# TIDA-010056_Page2.net
KiCad netlist of a schematic drawn in Altium Designer
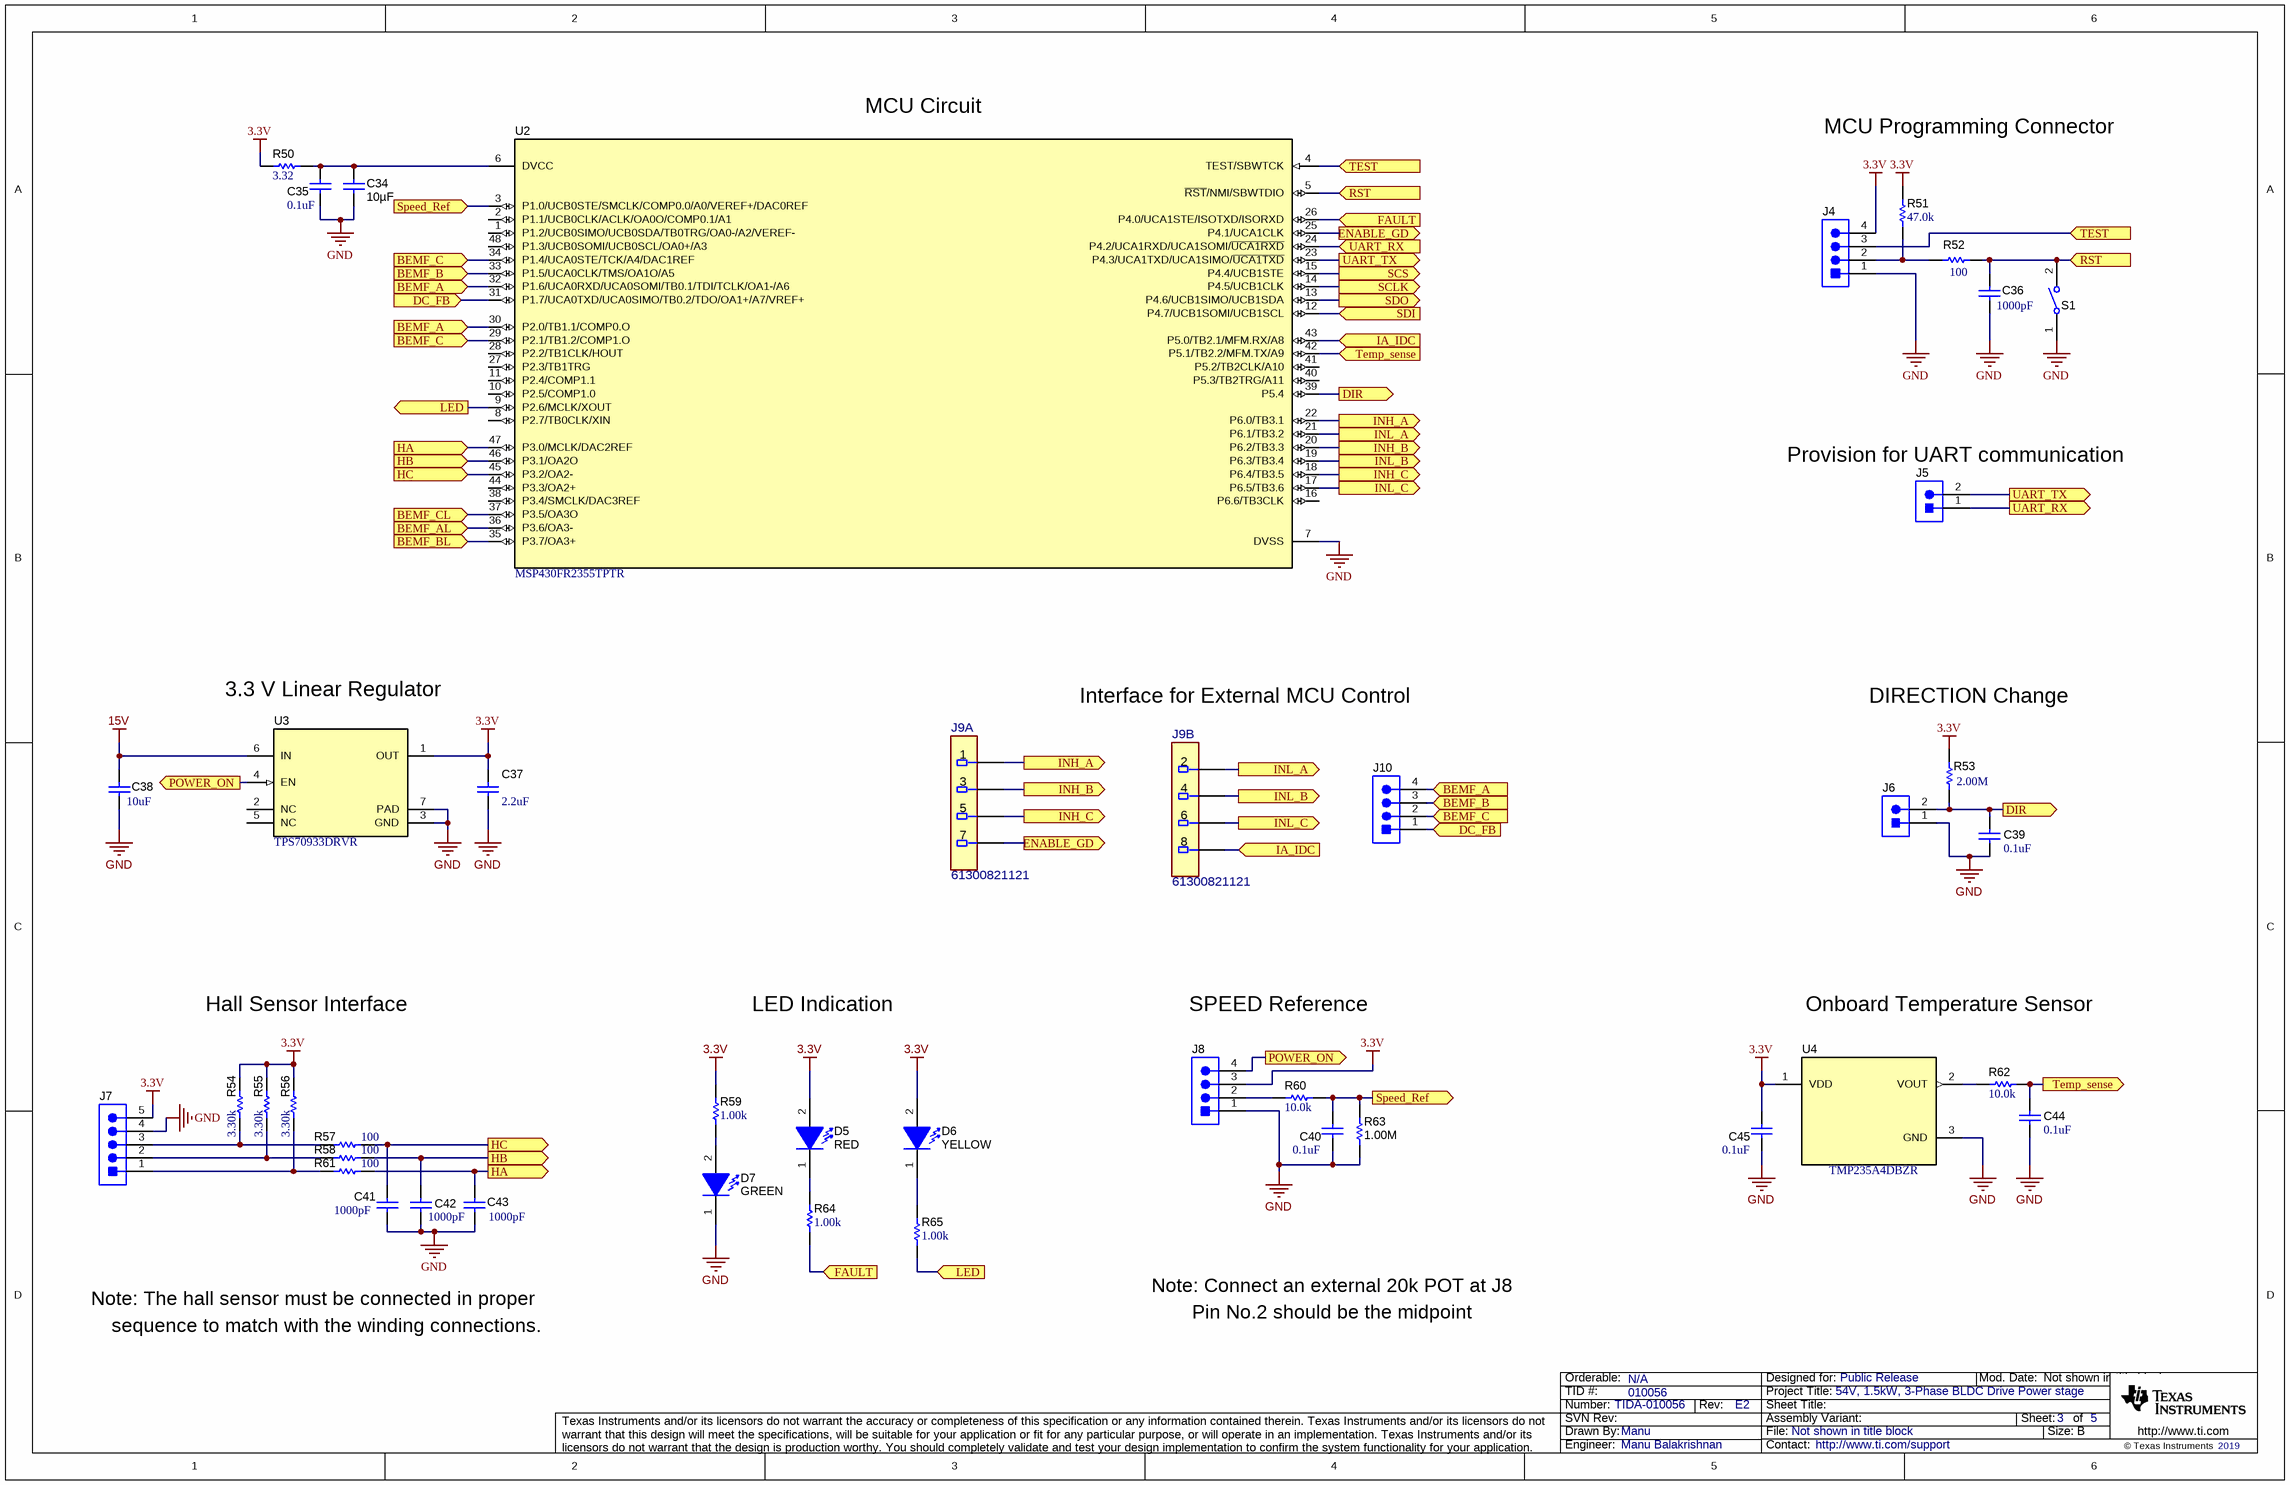
[diagram p0: TIDA-010056_Page2.SchDoc]

(export (version "E")
  (design (tool "Eeschema 10.0.6"))
  (components
    (comp (ref "C34")
      (value "GRM188R61A106KE69D")
      (footprint "0603")
      (description "CAP, CERM, 10 µF, 10 V,+/- 10%, X5R, 0603")
      (fields (field (name "MANUFACTURER") "MuRata") (field (name "VALUEDISPLAYED") "10µF"))
      (libsource (lib "Altium Vault - TI") (part "Capacitor"))
    )
    (comp (ref "C35")
      (value "GCM155R71A104KA55D")
      (footprint "0402")
      (description "CAP, CERM, 0.1 uF, 10 V, +/- 10%, X7R, AEC-Q200 Grade 1, 0402")
      (fields
        (field (name "MANUFACTURER") "MuRata")
        (field (name "VALUEDISPLAYED") "0.1uF")
        (field (name "PUBLISHER") "Texas Instruments")
      )
      (libsource (lib "Altium Vault - TI") (part "Capacitor"))
    )
    (comp (ref "C36")
      (value "GRM155R71C102KA01D")
      (footprint "0402")
      (description "CAP, CERM, 1000 pF, 16 V, +/- 10%, X7R, 0402")
      (fields
        (field (name "MANUFACTURER") "MuRata")
        (field (name "VALUEDISPLAYED") "1000pF")
        (field (name "PUBLISHER") "Texas Instruments")
      )
      (libsource (lib "Altium Vault - TI") (part "Capacitor"))
    )
    (comp (ref "C37")
      (value "885012105013")
      (footprint "0402")
      (description "CAP, CERM, 2.2 uF, 10 V, +/- 20%, X5R, 0402")
      (fields
        (field (name "MANUFACTURER") "Wurth Elektronik")
        (field (name "VALUEDISPLAYED") "2.2uF")
        (field (name "PUBLISHER") "Texas Instruments")
      )
      (libsource (lib "Altium Vault - TI") (part "Capacitor"))
    )
    (comp (ref "C38")
      (value "C3216X7R1V106M160AC")
      (footprint "1206_190")
      (description "CAP, CERM, 10 uF, 35 V, +/- 20%, X7R, 1206_190")
      (fields
        (field (name "MANUFACTURER") "TDK")
        (field (name "VALUEDISPLAYED") "10uF")
        (field (name "PUBLISHER") "Texas Instruments")
      )
      (libsource (lib "Altium Vault - TI") (part "Capacitor"))
    )
    (comp (ref "C39")
      (value "GCM155R71A104KA55D")
      (footprint "0402")
      (description "CAP, CERM, 0.1 uF, 10 V, +/- 10%, X7R, AEC-Q200 Grade 1, 0402")
      (fields
        (field (name "MANUFACTURER") "MuRata")
        (field (name "VALUEDISPLAYED") "0.1uF")
        (field (name "PUBLISHER") "Texas Instruments")
      )
      (libsource (lib "Altium Vault - TI") (part "Capacitor"))
    )
    (comp (ref "C40")
      (value "GCM155R71A104KA55D")
      (footprint "0402")
      (description "CAP, CERM, 0.1 uF, 10 V, +/- 10%, X7R, AEC-Q200 Grade 1, 0402")
      (fields
        (field (name "MANUFACTURER") "MuRata")
        (field (name "VALUEDISPLAYED") "0.1uF")
        (field (name "PUBLISHER") "Texas Instruments")
      )
      (libsource (lib "Altium Vault - TI") (part "Capacitor"))
    )
    (comp (ref "C41")
      (value "GRM155R71C102KA01D")
      (footprint "0402")
      (description "CAP, CERM, 1000 pF, 16 V, +/- 10%, X7R, 0402")
      (fields
        (field (name "MANUFACTURER") "MuRata")
        (field (name "VALUEDISPLAYED") "1000pF")
        (field (name "PUBLISHER") "Texas Instruments")
      )
      (libsource (lib "Altium Vault - TI") (part "Capacitor"))
    )
    (comp (ref "C42")
      (value "GRM155R71C102KA01D")
      (footprint "0402")
      (description "CAP, CERM, 1000 pF, 16 V, +/- 10%, X7R, 0402")
      (fields
        (field (name "MANUFACTURER") "MuRata")
        (field (name "VALUEDISPLAYED") "1000pF")
        (field (name "PUBLISHER") "Texas Instruments")
      )
      (libsource (lib "Altium Vault - TI") (part "Capacitor"))
    )
    (comp (ref "C43")
      (value "GRM155R71C102KA01D")
      (footprint "0402")
      (description "CAP, CERM, 1000 pF, 16 V, +/- 10%, X7R, 0402")
      (fields
        (field (name "MANUFACTURER") "MuRata")
        (field (name "VALUEDISPLAYED") "1000pF")
        (field (name "PUBLISHER") "Texas Instruments")
      )
      (libsource (lib "Altium Vault - TI") (part "Capacitor"))
    )
    (comp (ref "C44")
      (value "GCM155R71A104KA55D")
      (footprint "0402")
      (description "CAP, CERM, 0.1 uF, 10 V, +/- 10%, X7R, AEC-Q200 Grade 1, 0402")
      (fields
        (field (name "MANUFACTURER") "MuRata")
        (field (name "VALUEDISPLAYED") "0.1uF")
        (field (name "PUBLISHER") "Texas Instruments")
      )
      (libsource (lib "Altium Vault - TI") (part "Capacitor"))
    )
    (comp (ref "C45")
      (value "GCM155R71A104KA55D")
      (footprint "0402")
      (description "CAP, CERM, 0.1 uF, 10 V, +/- 10%, X7R, AEC-Q200 Grade 1, 0402")
      (fields
        (field (name "MANUFACTURER") "MuRata")
        (field (name "VALUEDISPLAYED") "0.1uF")
        (field (name "PUBLISHER") "Texas Instruments")
      )
      (libsource (lib "Altium Vault - TI") (part "Capacitor"))
    )
    (comp (ref "D5")
      (value "RED")
      (footprint "WL-SMCW_GREEN")
      (description "LED RED CLEAR 0603 SMD")
      (fields
        (field (name "MANUFACTURER") "Wurth Elektronics Inc")
        (field (name "PARTNUMBER") "150060RS75000")
        (field (name "PUBLISHER") "Texas Instruments")
      )
      (libsource (lib "LED") (part "150060GS75000"))
    )
    (comp (ref "D6")
      (value "YELLOW")
      (footprint "WL-SMCW_GREEN")
      (description "LED YELLOW CLEAR 0603 SMD")
      (fields
        (field (name "MANUFACTURER") "Wurth Elektronics Inc")
        (field (name "PARTNUMBER") "150060YS75000")
        (field (name "PUBLISHER") "Texas Instruments")
      )
      (libsource (lib "LED") (part "150060GS75000"))
    )
    (comp (ref "D7")
      (value "GREEN")
      (footprint "WL-SMCW_GREEN")
      (description "LED, Green, SMD")
      (fields
        (field (name "MANUFACTURER") "Wurth Elektronics Inc")
        (field (name "PARTNUMBER") "150060GS75000")
        (field (name "PUBLISHER") "Texas Instruments")
      )
      (libsource (lib "LED") (part "150060GS75000"))
    )
    (comp (ref "J4")
      (value "61300411121")
      (footprint "WURTH_61300411121")
      (description "Header, 2.54 mm, 4x1, Gold, TH")
      (fields (field (name "MANUFACTURER") "Wurth Elektronik"))
      (libsource (lib "Altium Vault - TI") (part "Header_4x1"))
    )
    (comp (ref "J5")
      (value "61300211121")
      (footprint "WURTH_61300211121")
      (description "Header, 2.54 mm, 2x1, Gold, TH")
      (fields (field (name "MANUFACTURER") "Wurth Elektronik"))
      (libsource (lib "Altium Vault - TI") (part "Header_2x1"))
    )
    (comp (ref "J6")
      (value "61300211121")
      (footprint "WURTH_61300211121")
      (description "Header, 2.54 mm, 2x1, Gold, TH")
      (fields (field (name "MANUFACTURER") "Wurth Elektronik"))
      (libsource (lib "Altium Vault - TI") (part "Header_2x1"))
    )
    (comp (ref "J7")
      (value "61300511121")
      (footprint "Wurth_61300511121")
      (description "Header, 2.54mm, 5x1, Gold, TH")
      (fields (field (name "MANUFACTURER") "Wurth Elektronik"))
      (libsource (lib "Altium Vault - TI") (part "Header_5x1"))
    )
    (comp (ref "J8")
      (value "61300411121")
      (footprint "WURTH_61300411121")
      (description "Header, 2.54 mm, 4x1, Gold, TH")
      (fields (field (name "MANUFACTURER") "Wurth Elektronik"))
      (libsource (lib "Altium Vault - TI") (part "Header_4x1"))
    )
    (comp (ref "J9")
      (value "61300821121")
      (footprint "FP-61300821121_HDR8-MFG")
      (description "CONN HEADER VERT 8POS 2.54MM")
      (fields (field (name "MANUFACTURER") "Wurth Electronics"))
      (libsource (lib "Altium Vault - TI") (part "SYM-61300821121"))
    )
    (comp (ref "J10")
      (value "61300411121")
      (footprint "WURTH_61300411121")
      (description "Header, 2.54 mm, 4x1, Gold, TH")
      (fields (field (name "MANUFACTURER") "Wurth Elektronik"))
      (libsource (lib "Altium Vault - TI") (part "Header_4x1"))
    )
    (comp (ref "R50")
      (value "CRCW04023R32FKED")
      (footprint "0402")
      (description "RES, 3.32, 1%, 0.063 W, AEC-Q200 Grade 0, 0402")
      (fields (field (name "MANUFACTURER") "Vishay-Dale") (field (name "VALUEDISPLAYED") "3.32"))
      (libsource (lib "Altium Vault - TI") (part "Resistor"))
    )
    (comp (ref "R51")
      (value "RC0402FR-0747KL")
      (footprint "0402")
      (description "RES, 47.0 k, 1%, 0.0625 W, 0402")
      (fields
        (field (name "MANUFACTURER") "Yageo America")
        (field (name "VALUEDISPLAYED") "47.0k")
        (field (name "PUBLISHER") "Texas Instruments")
      )
      (libsource (lib "Altium Vault - TI") (part "Resistor"))
    )
    (comp (ref "R52")
      (value "ERJ-2GEJ101X")
      (footprint "0402")
      (description "RES, 100, 5%, 0.1 W, AEC-Q200 Grade 0, 0402")
      (fields
        (field (name "MANUFACTURER") "Panasonic")
        (field (name "VALUEDISPLAYED") "100")
        (field (name "PUBLISHER") "Texas Instruments")
      )
      (libsource (lib "Altium Vault - TI") (part "Resistor"))
    )
    (comp (ref "R53")
      (value "CRCW04022M00FKED")
      (footprint "0402")
      (description "RES, 2.00 M, 1%, 0.063 W, AEC-Q200 Grade 0, 0402")
      (fields (field (name "MANUFACTURER") "Vishay-Dale") (field (name "VALUEDISPLAYED") "2.00M"))
      (libsource (lib "Altium Vault - TI") (part "Resistor"))
    )
    (comp (ref "R54")
      (value "ERJ-2RKF3301X")
      (footprint "0402")
      (description "RES, 3.30 k, 1%, 0.1 W, AEC-Q200 Grade 0, 0402")
      (fields
        (field (name "MANUFACTURER") "Panasonic")
        (field (name "VALUEDISPLAYED") "3.30k")
        (field (name "PUBLISHER") "Texas Instruments")
      )
      (libsource (lib "Altium Vault - TI") (part "Resistor"))
    )
    (comp (ref "R55")
      (value "ERJ-2RKF3301X")
      (footprint "0402")
      (description "RES, 3.30 k, 1%, 0.1 W, AEC-Q200 Grade 0, 0402")
      (fields
        (field (name "MANUFACTURER") "Panasonic")
        (field (name "VALUEDISPLAYED") "3.30k")
        (field (name "PUBLISHER") "Texas Instruments")
      )
      (libsource (lib "Altium Vault - TI") (part "Resistor"))
    )
    (comp (ref "R56")
      (value "ERJ-2RKF3301X")
      (footprint "0402")
      (description "RES, 3.30 k, 1%, 0.1 W, AEC-Q200 Grade 0, 0402")
      (fields
        (field (name "MANUFACTURER") "Panasonic")
        (field (name "VALUEDISPLAYED") "3.30k")
        (field (name "PUBLISHER") "Texas Instruments")
      )
      (libsource (lib "Altium Vault - TI") (part "Resistor"))
    )
    (comp (ref "R57")
      (value "ERJ-2GEJ101X")
      (footprint "0402")
      (description "RES, 100, 5%, 0.1 W, AEC-Q200 Grade 0, 0402")
      (fields
        (field (name "MANUFACTURER") "Panasonic")
        (field (name "VALUEDISPLAYED") "100")
        (field (name "PUBLISHER") "Texas Instruments")
      )
      (libsource (lib "Altium Vault - TI") (part "Resistor"))
    )
    (comp (ref "R58")
      (value "ERJ-2GEJ101X")
      (footprint "0402")
      (description "RES, 100, 5%, 0.1 W, AEC-Q200 Grade 0, 0402")
      (fields
        (field (name "MANUFACTURER") "Panasonic")
        (field (name "VALUEDISPLAYED") "100")
        (field (name "PUBLISHER") "Texas Instruments")
      )
      (libsource (lib "Altium Vault - TI") (part "Resistor"))
    )
    (comp (ref "R59")
      (value "ERJ-2RKF1001X")
      (footprint "0402")
      (description "RES, 1.00 k, 1%, 0.1 W, 0402")
      (fields
        (field (name "MANUFACTURER") "Panasonic")
        (field (name "VALUEDISPLAYED") "1.00k")
        (field (name "PUBLISHER") "Texas Instruments")
      )
      (libsource (lib "Altium Vault - TI") (part "Resistor"))
    )
    (comp (ref "R60")
      (value "ERJ-2RKF1002X")
      (footprint "0402")
      (description "RES, 10.0 k, 1%, 0.1 W, 0402")
      (fields
        (field (name "MANUFACTURER") "Panasonic")
        (field (name "VALUEDISPLAYED") "10.0k")
        (field (name "PUBLISHER") "Texas Instruments")
      )
      (libsource (lib "Altium Vault - TI") (part "Resistor"))
    )
    (comp (ref "R61")
      (value "ERJ-2GEJ101X")
      (footprint "0402")
      (description "RES, 100, 5%, 0.1 W, AEC-Q200 Grade 0, 0402")
      (fields
        (field (name "MANUFACTURER") "Panasonic")
        (field (name "VALUEDISPLAYED") "100")
        (field (name "PUBLISHER") "Texas Instruments")
      )
      (libsource (lib "Altium Vault - TI") (part "Resistor"))
    )
    (comp (ref "R62")
      (value "ERJ-2RKF1002X")
      (footprint "0402")
      (description "RES, 10.0 k, 1%, 0.1 W, 0402")
      (fields
        (field (name "MANUFACTURER") "Panasonic")
        (field (name "VALUEDISPLAYED") "10.0k")
        (field (name "PUBLISHER") "Texas Instruments")
      )
      (libsource (lib "Altium Vault - TI") (part "Resistor"))
    )
    (comp (ref "R63")
      (value "ERJ-2RKF1004X")
      (footprint "0402")
      (description "RES, 1.00 M, 1%, 0.1 W, 0402")
      (fields
        (field (name "MANUFACTURER") "Panasonic")
        (field (name "VALUEDISPLAYED") "1.00M")
        (field (name "PUBLISHER") "Texas Instruments")
      )
      (libsource (lib "Altium Vault - TI") (part "Resistor"))
    )
    (comp (ref "R64")
      (value "ERJ-2RKF1001X")
      (footprint "0402")
      (description "RES, 1.00 k, 1%, 0.1 W, 0402")
      (fields
        (field (name "MANUFACTURER") "Panasonic")
        (field (name "VALUEDISPLAYED") "1.00k")
        (field (name "PUBLISHER") "Texas Instruments")
      )
      (libsource (lib "Altium Vault - TI") (part "Resistor"))
    )
    (comp (ref "R65")
      (value "ERJ-2RKF1001X")
      (footprint "0402")
      (description "RES, 1.00 k, 1%, 0.1 W, 0402")
      (fields
        (field (name "MANUFACTURER") "Panasonic")
        (field (name "VALUEDISPLAYED") "1.00k")
        (field (name "PUBLISHER") "Texas Instruments")
      )
      (libsource (lib "Altium Vault - TI") (part "Resistor"))
    )
    (comp (ref "S1")
      (value "434121025816")
      (footprint "SW_434121025816")
      (description "Switch, Tactile, SPST, 12 V, SMD")
      (fields (field (name "MANUFACTURER") "Wurth Elektronik") (field (name "PUBLISHER") "Texas Instruments"))
      (libsource (lib "Altium Vault - TI") (part "SW_SPST-single"))
    )
    (comp (ref "U2")
      (value "MSP430FR2355TPTR")
      (footprint "PT0048A_N")
      (description "Mixed-Signal Microcontroller, PT0048A (LQFP-48)")
      (fields
        (field (name "PARTNUMBER") "MSP430FR2355TPTR")
        (field (name "MANUFACTURER") "Texas Instruments")
        (field (name "PUBLISHER") "Texas Instruments")
      )
      (libsource (lib "Altium Vault - TI") (part "MSP430FR235xPT"))
    )
    (comp (ref "U3")
      (value "TPS70933DRVR")
      (footprint "DRV0006A")
      (fields
        (field (name "ALTERNATE PARTNUMBER") "TPS70933DRVT")
        (field (name "MANUFACTURER") "Texas Instruments")
        (field (name "PARTNUMBER") "TPS70933DRVR")
        (field (name "PUBLISHER") "Texas Instruments")
      )
      (libsource (lib "Altium Vault - TI") (part "TPS709XXDRV"))
    )
    (comp (ref "U4")
      (value "TMP235A4DBZR")
      (footprint "DBZ0003A_N")
      (description "TMP235A4DBZR, DBZ0003A (SOP-3)")
      (fields
        (field (name "MANUFACTURER") "Texas Instruments")
        (field (name "PARTNUMBER") "TMP235A4DBZR")
        (field (name "PUBLISHER") "Texas Instruments")
      )
      (libsource (lib "Altium Vault - TI") (part "TMP235DBZ"))
    )
  )
  (nets
    (net (code "1") (name "/BEMF_A") (class "Default")
      (node (ref "J10") (pin "4") (pinfunction "4_4") (pintype "passive"))
      (node (ref "U2") (pin "30") (pinfunction "P2.0/TB1.1/COMP0.O_30") (pintype "bidirectional"))
      (node (ref "U2") (pin "32") (pinfunction "P1.6/UCA0RXD/UCA0SOMI/TB0.1/TDI/TCLK/OA1-/A6_32") (pintype "bidirectional"))
    )
    (net (code "2") (name "/BEMF_AL") (class "Default")
      (node (ref "U2") (pin "36") (pinfunction "P3.6/OA3-_36") (pintype "bidirectional"))
    )
    (net (code "3") (name "/BEMF_B") (class "Default")
      (node (ref "J10") (pin "3") (pinfunction "3_3") (pintype "passive"))
      (node (ref "U2") (pin "33") (pinfunction "P1.5/UCA0CLK/TMS/OA1O/A5_33") (pintype "bidirectional"))
    )
    (net (code "4") (name "/BEMF_BL") (class "Default")
      (node (ref "U2") (pin "35") (pinfunction "P3.7/OA3+_35") (pintype "bidirectional"))
    )
    (net (code "5") (name "/BEMF_C") (class "Default")
      (node (ref "J10") (pin "2") (pinfunction "2_2") (pintype "passive"))
      (node (ref "U2") (pin "29") (pinfunction "P2.1/TB1.2/COMP1.O_29") (pintype "bidirectional"))
      (node (ref "U2") (pin "34") (pinfunction "P1.4/UCA0STE/TCK/A4/DAC1REF_34") (pintype "bidirectional"))
    )
    (net (code "6") (name "/BEMF_CL") (class "Default")
      (node (ref "U2") (pin "37") (pinfunction "P3.5/OA3O_37") (pintype "bidirectional"))
    )
    (net (code "7") (name "/DC_FB") (class "Default")
      (node (ref "J10") (pin "1") (pinfunction "1_1") (pintype "passive"))
      (node (ref "U2") (pin "31") (pinfunction "P1.7/UCA0TXD/UCA0SIMO/TB0.2/TDO/OA1+/A7/VREF+_31") (pintype "bidirectional"))
    )
    (net (code "8") (name "/DIR") (class "Default")
      (node (ref "C39") (pin "1") (pinfunction "1_1") (pintype "passive"))
      (node (ref "J6") (pin "2") (pinfunction "2_2") (pintype "passive"))
      (node (ref "R53") (pin "1") (pinfunction "1_1") (pintype "passive"))
      (node (ref "U2") (pin "39") (pinfunction "P5.4_39") (pintype "bidirectional"))
    )
    (net (code "9") (name "/ENABLE_GD") (class "Default")
      (node (ref "J9") (pin "7") (pinfunction "7_7") (pintype "passive"))
      (node (ref "U2") (pin "25") (pinfunction "P4.1/UCA1CLK_25") (pintype "bidirectional"))
    )
    (net (code "10") (name "/FAULT") (class "Default")
      (node (ref "R64") (pin "1") (pinfunction "1_1") (pintype "passive"))
      (node (ref "U2") (pin "26") (pinfunction "P4.0/UCA1STE/ISOTXD/ISORXD_26") (pintype "bidirectional"))
    )
    (net (code "11") (name "/HA") (class "Default")
      (node (ref "C43") (pin "1") (pinfunction "1_1") (pintype "passive"))
      (node (ref "R61") (pin "2") (pinfunction "2_2") (pintype "passive"))
      (node (ref "U2") (pin "47") (pinfunction "P3.0/MCLK/DAC2REF_47") (pintype "bidirectional"))
    )
    (net (code "12") (name "/HB") (class "Default")
      (node (ref "C42") (pin "1") (pinfunction "1_1") (pintype "passive"))
      (node (ref "R58") (pin "2") (pinfunction "2_2") (pintype "passive"))
      (node (ref "U2") (pin "46") (pinfunction "P3.1/OA2O_46") (pintype "bidirectional"))
    )
    (net (code "13") (name "/HC") (class "Default")
      (node (ref "C41") (pin "1") (pinfunction "1_1") (pintype "passive"))
      (node (ref "R57") (pin "2") (pinfunction "2_2") (pintype "passive"))
      (node (ref "U2") (pin "45") (pinfunction "P3.2/OA2-_45") (pintype "bidirectional"))
    )
    (net (code "14") (name "/IA_IDC") (class "Default")
      (node (ref "J9") (pin "8") (pinfunction "8_8") (pintype "passive"))
      (node (ref "U2") (pin "43") (pinfunction "P5.0/TB2.1/MFM.RX/A8_43") (pintype "bidirectional"))
    )
    (net (code "15") (name "/INH_A") (class "Default")
      (node (ref "J9") (pin "1") (pinfunction "1_1") (pintype "passive"))
      (node (ref "U2") (pin "22") (pinfunction "P6.0/TB3.1_22") (pintype "bidirectional"))
    )
    (net (code "16") (name "/INH_B") (class "Default")
      (node (ref "J9") (pin "3") (pinfunction "3_3") (pintype "passive"))
      (node (ref "U2") (pin "20") (pinfunction "P6.2/TB3.3_20") (pintype "bidirectional"))
    )
    (net (code "17") (name "/INH_C") (class "Default")
      (node (ref "J9") (pin "5") (pinfunction "5_5") (pintype "passive"))
      (node (ref "U2") (pin "18") (pinfunction "P6.4/TB3.5_18") (pintype "bidirectional"))
    )
    (net (code "18") (name "/INL_A") (class "Default")
      (node (ref "J9") (pin "2") (pinfunction "2_2") (pintype "passive"))
      (node (ref "U2") (pin "21") (pinfunction "P6.1/TB3.2_21") (pintype "bidirectional"))
    )
    (net (code "19") (name "/INL_B") (class "Default")
      (node (ref "J9") (pin "4") (pinfunction "4_4") (pintype "passive"))
      (node (ref "U2") (pin "19") (pinfunction "P6.3/TB3.4_19") (pintype "bidirectional"))
    )
    (net (code "20") (name "/INL_C") (class "Default")
      (node (ref "J9") (pin "6") (pinfunction "6_6") (pintype "passive"))
      (node (ref "U2") (pin "17") (pinfunction "P6.5/TB3.6_17") (pintype "bidirectional"))
    )
    (net (code "21") (name "/LED") (class "Default")
      (node (ref "R65") (pin "1") (pinfunction "1_1") (pintype "passive"))
      (node (ref "U2") (pin "9") (pinfunction "P2.6/MCLK/XOUT_9") (pintype "bidirectional"))
    )
    (net (code "22") (name "/POWER_ON") (class "Default")
      (node (ref "J8") (pin "4") (pinfunction "4_4") (pintype "passive"))
      (node (ref "U3") (pin "4") (pinfunction "EN_4") (pintype "input"))
    )
    (net (code "23") (name "/RST") (class "Default")
      (node (ref "C36") (pin "1") (pinfunction "1_1") (pintype "passive"))
      (node (ref "R52") (pin "2") (pinfunction "2_2") (pintype "passive"))
      (node (ref "S1") (pin "2") (pinfunction "2_2") (pintype "passive"))
      (node (ref "U2") (pin "5") (pinfunction "~{RST}/NMI/SBWTDIO_5") (pintype "bidirectional"))
    )
    (net (code "24") (name "/SCLK") (class "Default")
      (node (ref "U2") (pin "14") (pinfunction "P4.5/UCB1CLK_14") (pintype "bidirectional"))
    )
    (net (code "25") (name "/SCS") (class "Default")
      (node (ref "U2") (pin "15") (pinfunction "P4.4/UCB1STE_15") (pintype "bidirectional"))
    )
    (net (code "26") (name "/SDI") (class "Default")
      (node (ref "U2") (pin "12") (pinfunction "P4.7/UCB1SOMI/UCB1SCL_12") (pintype "bidirectional"))
    )
    (net (code "27") (name "/SDO") (class "Default")
      (node (ref "U2") (pin "13") (pinfunction "P4.6/UCB1SIMO/UCB1SDA_13") (pintype "bidirectional"))
    )
    (net (code "28") (name "/Speed_Ref") (class "Default")
      (node (ref "C40") (pin "1") (pinfunction "1_1") (pintype "passive"))
      (node (ref "R60") (pin "1") (pinfunction "1_1") (pintype "passive"))
      (node (ref "R63") (pin "2") (pinfunction "2_2") (pintype "passive"))
      (node (ref "U2") (pin "3") (pinfunction "P1.0/UCB0STE/SMCLK/COMP0.0/A0/VEREF+/DAC0REF_3") (pintype "bidirectional"))
    )
    (net (code "29") (name "/TEST") (class "Default")
      (node (ref "J4") (pin "3") (pinfunction "3_3") (pintype "passive"))
      (node (ref "U2") (pin "4") (pinfunction "TEST/SBWTCK_4") (pintype "input"))
    )
    (net (code "30") (name "/Temp_sense") (class "Default")
      (node (ref "C44") (pin "1") (pinfunction "1_1") (pintype "passive"))
      (node (ref "R62") (pin "1") (pinfunction "1_1") (pintype "passive"))
      (node (ref "U2") (pin "42") (pinfunction "P5.1/TB2.2/MFM.TX/A9_42") (pintype "bidirectional"))
    )
    (net (code "31") (name "/UART_RX") (class "Default")
      (node (ref "J5") (pin "1") (pinfunction "1_1") (pintype "passive"))
      (node (ref "U2") (pin "24") (pinfunction "P4.2/UCA1RXD/UCA1SOMI/~{UCA1RXD}_24") (pintype "bidirectional"))
    )
    (net (code "32") (name "/UART_TX") (class "Default")
      (node (ref "J5") (pin "2") (pinfunction "2_2") (pintype "passive"))
      (node (ref "U2") (pin "23") (pinfunction "P4.3/UCA1TXD/UCA1SIMO/~{UCA1TXD}_23") (pintype "bidirectional"))
    )
    (net (code "33") (name "3.3V") (class "Default")
      (node (ref "C37") (pin "1") (pinfunction "1_1") (pintype "passive"))
      (node (ref "C45") (pin "1") (pinfunction "1_1") (pintype "passive"))
      (node (ref "D5") (pin "2") (pinfunction "A_2") (pintype "passive"))
      (node (ref "D6") (pin "2") (pinfunction "A_2") (pintype "passive"))
      (node (ref "J4") (pin "4") (pinfunction "4_4") (pintype "passive"))
      (node (ref "J7") (pin "5") (pinfunction "5_5") (pintype "passive"))
      (node (ref "J8") (pin "3") (pinfunction "3_3") (pintype "passive"))
      (node (ref "R50") (pin "1") (pinfunction "1_1") (pintype "passive"))
      (node (ref "R51") (pin "2") (pinfunction "2_2") (pintype "passive"))
      (node (ref "R53") (pin "2") (pinfunction "2_2") (pintype "passive"))
      (node (ref "R54") (pin "2") (pinfunction "2_2") (pintype "passive"))
      (node (ref "R55") (pin "2") (pinfunction "2_2") (pintype "passive"))
      (node (ref "R56") (pin "2") (pinfunction "2_2") (pintype "passive"))
      (node (ref "R59") (pin "2") (pinfunction "2_2") (pintype "passive"))
      (node (ref "U3") (pin "1") (pinfunction "OUT_1") (pintype "power_in"))
      (node (ref "U4") (pin "1") (pinfunction "VDD_1") (pintype "power_in"))
    )
    (net (code "34") (name "15V") (class "Default")
      (node (ref "C38") (pin "1") (pinfunction "1_1") (pintype "passive"))
      (node (ref "U3") (pin "6") (pinfunction "IN_6") (pintype "power_in"))
    )
    (net (code "35") (name "GND") (class "Default")
      (node (ref "C34") (pin "2") (pinfunction "2_2") (pintype "passive"))
      (node (ref "C35") (pin "2") (pinfunction "2_2") (pintype "passive"))
      (node (ref "C36") (pin "2") (pinfunction "2_2") (pintype "passive"))
      (node (ref "C37") (pin "2") (pinfunction "2_2") (pintype "passive"))
      (node (ref "C38") (pin "2") (pinfunction "2_2") (pintype "passive"))
      (node (ref "C39") (pin "2") (pinfunction "2_2") (pintype "passive"))
      (node (ref "C40") (pin "2") (pinfunction "2_2") (pintype "passive"))
      (node (ref "C41") (pin "2") (pinfunction "2_2") (pintype "passive"))
      (node (ref "C42") (pin "2") (pinfunction "2_2") (pintype "passive"))
      (node (ref "C43") (pin "2") (pinfunction "2_2") (pintype "passive"))
      (node (ref "C44") (pin "2") (pinfunction "2_2") (pintype "passive"))
      (node (ref "C45") (pin "2") (pinfunction "2_2") (pintype "passive"))
      (node (ref "D7") (pin "1") (pinfunction "K_1") (pintype "passive"))
      (node (ref "J4") (pin "1") (pinfunction "1_1") (pintype "passive"))
      (node (ref "J6") (pin "1") (pinfunction "1_1") (pintype "passive"))
      (node (ref "J7") (pin "4") (pinfunction "4_4") (pintype "passive"))
      (node (ref "J8") (pin "1") (pinfunction "1_1") (pintype "passive"))
      (node (ref "R63") (pin "1") (pinfunction "1_1") (pintype "passive"))
      (node (ref "S1") (pin "1") (pinfunction "1_1") (pintype "passive"))
      (node (ref "U2") (pin "7") (pinfunction "DVSS_7") (pintype "power_in"))
      (node (ref "U3") (pin "3") (pinfunction "GND_3") (pintype "power_in"))
      (node (ref "U3") (pin "7") (pinfunction "PAD_7") (pintype "power_in"))
      (node (ref "U4") (pin "3") (pinfunction "GND_3") (pintype "power_in"))
    )
    (net (code "36") (name "Net-(D5-K)") (class "Default")
      (node (ref "D5") (pin "1") (pinfunction "K_1") (pintype "passive"))
      (node (ref "R64") (pin "2") (pinfunction "2_2") (pintype "passive"))
    )
    (net (code "37") (name "Net-(D6-K)") (class "Default")
      (node (ref "D6") (pin "1") (pinfunction "K_1") (pintype "passive"))
      (node (ref "R65") (pin "2") (pinfunction "2_2") (pintype "passive"))
    )
    (net (code "38") (name "Net-(D7-A)") (class "Default")
      (node (ref "D7") (pin "2") (pinfunction "A_2") (pintype "passive"))
      (node (ref "R59") (pin "1") (pinfunction "1_1") (pintype "passive"))
    )
    (net (code "39") (name "Net-(J4-Pad2)") (class "Default")
      (node (ref "J4") (pin "2") (pinfunction "2_2") (pintype "passive"))
      (node (ref "R51") (pin "1") (pinfunction "1_1") (pintype "passive"))
      (node (ref "R52") (pin "1") (pinfunction "1_1") (pintype "passive"))
    )
    (net (code "40") (name "Net-(J7-Pad1)") (class "Default")
      (node (ref "J7") (pin "1") (pinfunction "1_1") (pintype "passive"))
      (node (ref "R56") (pin "1") (pinfunction "1_1") (pintype "passive"))
      (node (ref "R61") (pin "1") (pinfunction "1_1") (pintype "passive"))
    )
    (net (code "41") (name "Net-(J7-Pad2)") (class "Default")
      (node (ref "J7") (pin "2") (pinfunction "2_2") (pintype "passive"))
      (node (ref "R55") (pin "1") (pinfunction "1_1") (pintype "passive"))
      (node (ref "R58") (pin "1") (pinfunction "1_1") (pintype "passive"))
    )
    (net (code "42") (name "Net-(J7-Pad3)") (class "Default")
      (node (ref "J7") (pin "3") (pinfunction "3_3") (pintype "passive"))
      (node (ref "R54") (pin "1") (pinfunction "1_1") (pintype "passive"))
      (node (ref "R57") (pin "1") (pinfunction "1_1") (pintype "passive"))
    )
    (net (code "43") (name "Net-(J8-Pad2)") (class "Default")
      (node (ref "J8") (pin "2") (pinfunction "2_2") (pintype "passive"))
      (node (ref "R60") (pin "2") (pinfunction "2_2") (pintype "passive"))
    )
    (net (code "44") (name "Net-(U2-DVCC)") (class "Default")
      (node (ref "C34") (pin "1") (pinfunction "1_1") (pintype "passive"))
      (node (ref "C35") (pin "1") (pinfunction "1_1") (pintype "passive"))
      (node (ref "R50") (pin "2") (pinfunction "2_2") (pintype "passive"))
      (node (ref "U2") (pin "6") (pinfunction "DVCC_6") (pintype "power_in"))
    )
    (net (code "45") (name "Net-(U4-VOUT)") (class "Default")
      (node (ref "R62") (pin "2") (pinfunction "2_2") (pintype "passive"))
      (node (ref "U4") (pin "2") (pinfunction "VOUT_2") (pintype "output"))
    )
    (net (code "46") (name "unconnected-(U2-P1.1{slash}UCB0CLK{slash}ACLK{slash}OA0O{slash}COMP0.1{slash}A1-Pad2)") (class "Default")
      (node (ref "U2") (pin "2") (pinfunction "P1.1/UCB0CLK/ACLK/OA0O/COMP0.1/A1_2") (pintype "bidirectional"))
    )
    (net (code "47") (name "unconnected-(U2-P1.2{slash}UCB0SIMO{slash}UCB0SDA{slash}TB0TRG{slash}OA0-{slash}A2{slash}VEREF--Pad1)") (class "Default")
      (node (ref "U2") (pin "1") (pinfunction "P1.2/UCB0SIMO/UCB0SDA/TB0TRG/OA0-/A2/VEREF-_1") (pintype "bidirectional"))
    )
    (net (code "48") (name "unconnected-(U2-P1.3{slash}UCB0SOMI{slash}UCB0SCL{slash}OA0+{slash}A3-Pad48)") (class "Default")
      (node (ref "U2") (pin "48") (pinfunction "P1.3/UCB0SOMI/UCB0SCL/OA0+/A3_48") (pintype "bidirectional"))
    )
    (net (code "49") (name "unconnected-(U2-P2.2{slash}TB1CLK{slash}HOUT-Pad28)") (class "Default")
      (node (ref "U2") (pin "28") (pinfunction "P2.2/TB1CLK/HOUT_28") (pintype "bidirectional"))
    )
    (net (code "50") (name "unconnected-(U2-P2.3{slash}TB1TRG-Pad27)") (class "Default")
      (node (ref "U2") (pin "27") (pinfunction "P2.3/TB1TRG_27") (pintype "bidirectional"))
    )
    (net (code "51") (name "unconnected-(U2-P2.4{slash}COMP1.1-Pad11)") (class "Default")
      (node (ref "U2") (pin "11") (pinfunction "P2.4/COMP1.1_11") (pintype "bidirectional"))
    )
    (net (code "52") (name "unconnected-(U2-P2.5{slash}COMP1.0-Pad10)") (class "Default")
      (node (ref "U2") (pin "10") (pinfunction "P2.5/COMP1.0_10") (pintype "bidirectional"))
    )
    (net (code "53") (name "unconnected-(U2-P2.7{slash}TB0CLK{slash}XIN-Pad8)") (class "Default")
      (node (ref "U2") (pin "8") (pinfunction "P2.7/TB0CLK/XIN_8") (pintype "bidirectional"))
    )
    (net (code "54") (name "unconnected-(U2-P3.3{slash}OA2+-Pad44)") (class "Default")
      (node (ref "U2") (pin "44") (pinfunction "P3.3/OA2+_44") (pintype "bidirectional"))
    )
    (net (code "55") (name "unconnected-(U2-P3.4{slash}SMCLK{slash}DAC3REF-Pad38)") (class "Default")
      (node (ref "U2") (pin "38") (pinfunction "P3.4/SMCLK/DAC3REF_38") (pintype "bidirectional"))
    )
    (net (code "56") (name "unconnected-(U2-P5.2{slash}TB2CLK{slash}A10-Pad41)") (class "Default")
      (node (ref "U2") (pin "41") (pinfunction "P5.2/TB2CLK/A10_41") (pintype "bidirectional"))
    )
    (net (code "57") (name "unconnected-(U2-P5.3{slash}TB2TRG{slash}A11-Pad40)") (class "Default")
      (node (ref "U2") (pin "40") (pinfunction "P5.3/TB2TRG/A11_40") (pintype "bidirectional"))
    )
    (net (code "58") (name "unconnected-(U2-P6.6{slash}TB3CLK-Pad16)") (class "Default")
      (node (ref "U2") (pin "16") (pinfunction "P6.6/TB3CLK_16") (pintype "bidirectional"))
    )
    (net (code "59") (name "unconnected-(U3-NC-Pad2)") (class "Default")
      (node (ref "U3") (pin "2") (pinfunction "NC_2") (pintype "passive"))
    )
    (net (code "60") (name "unconnected-(U3-NC-Pad5)") (class "Default")
      (node (ref "U3") (pin "5") (pinfunction "NC_5") (pintype "passive"))
    )
  )
)
